# default.net
KiCad netlist of a schematic drawn in Altium Designer
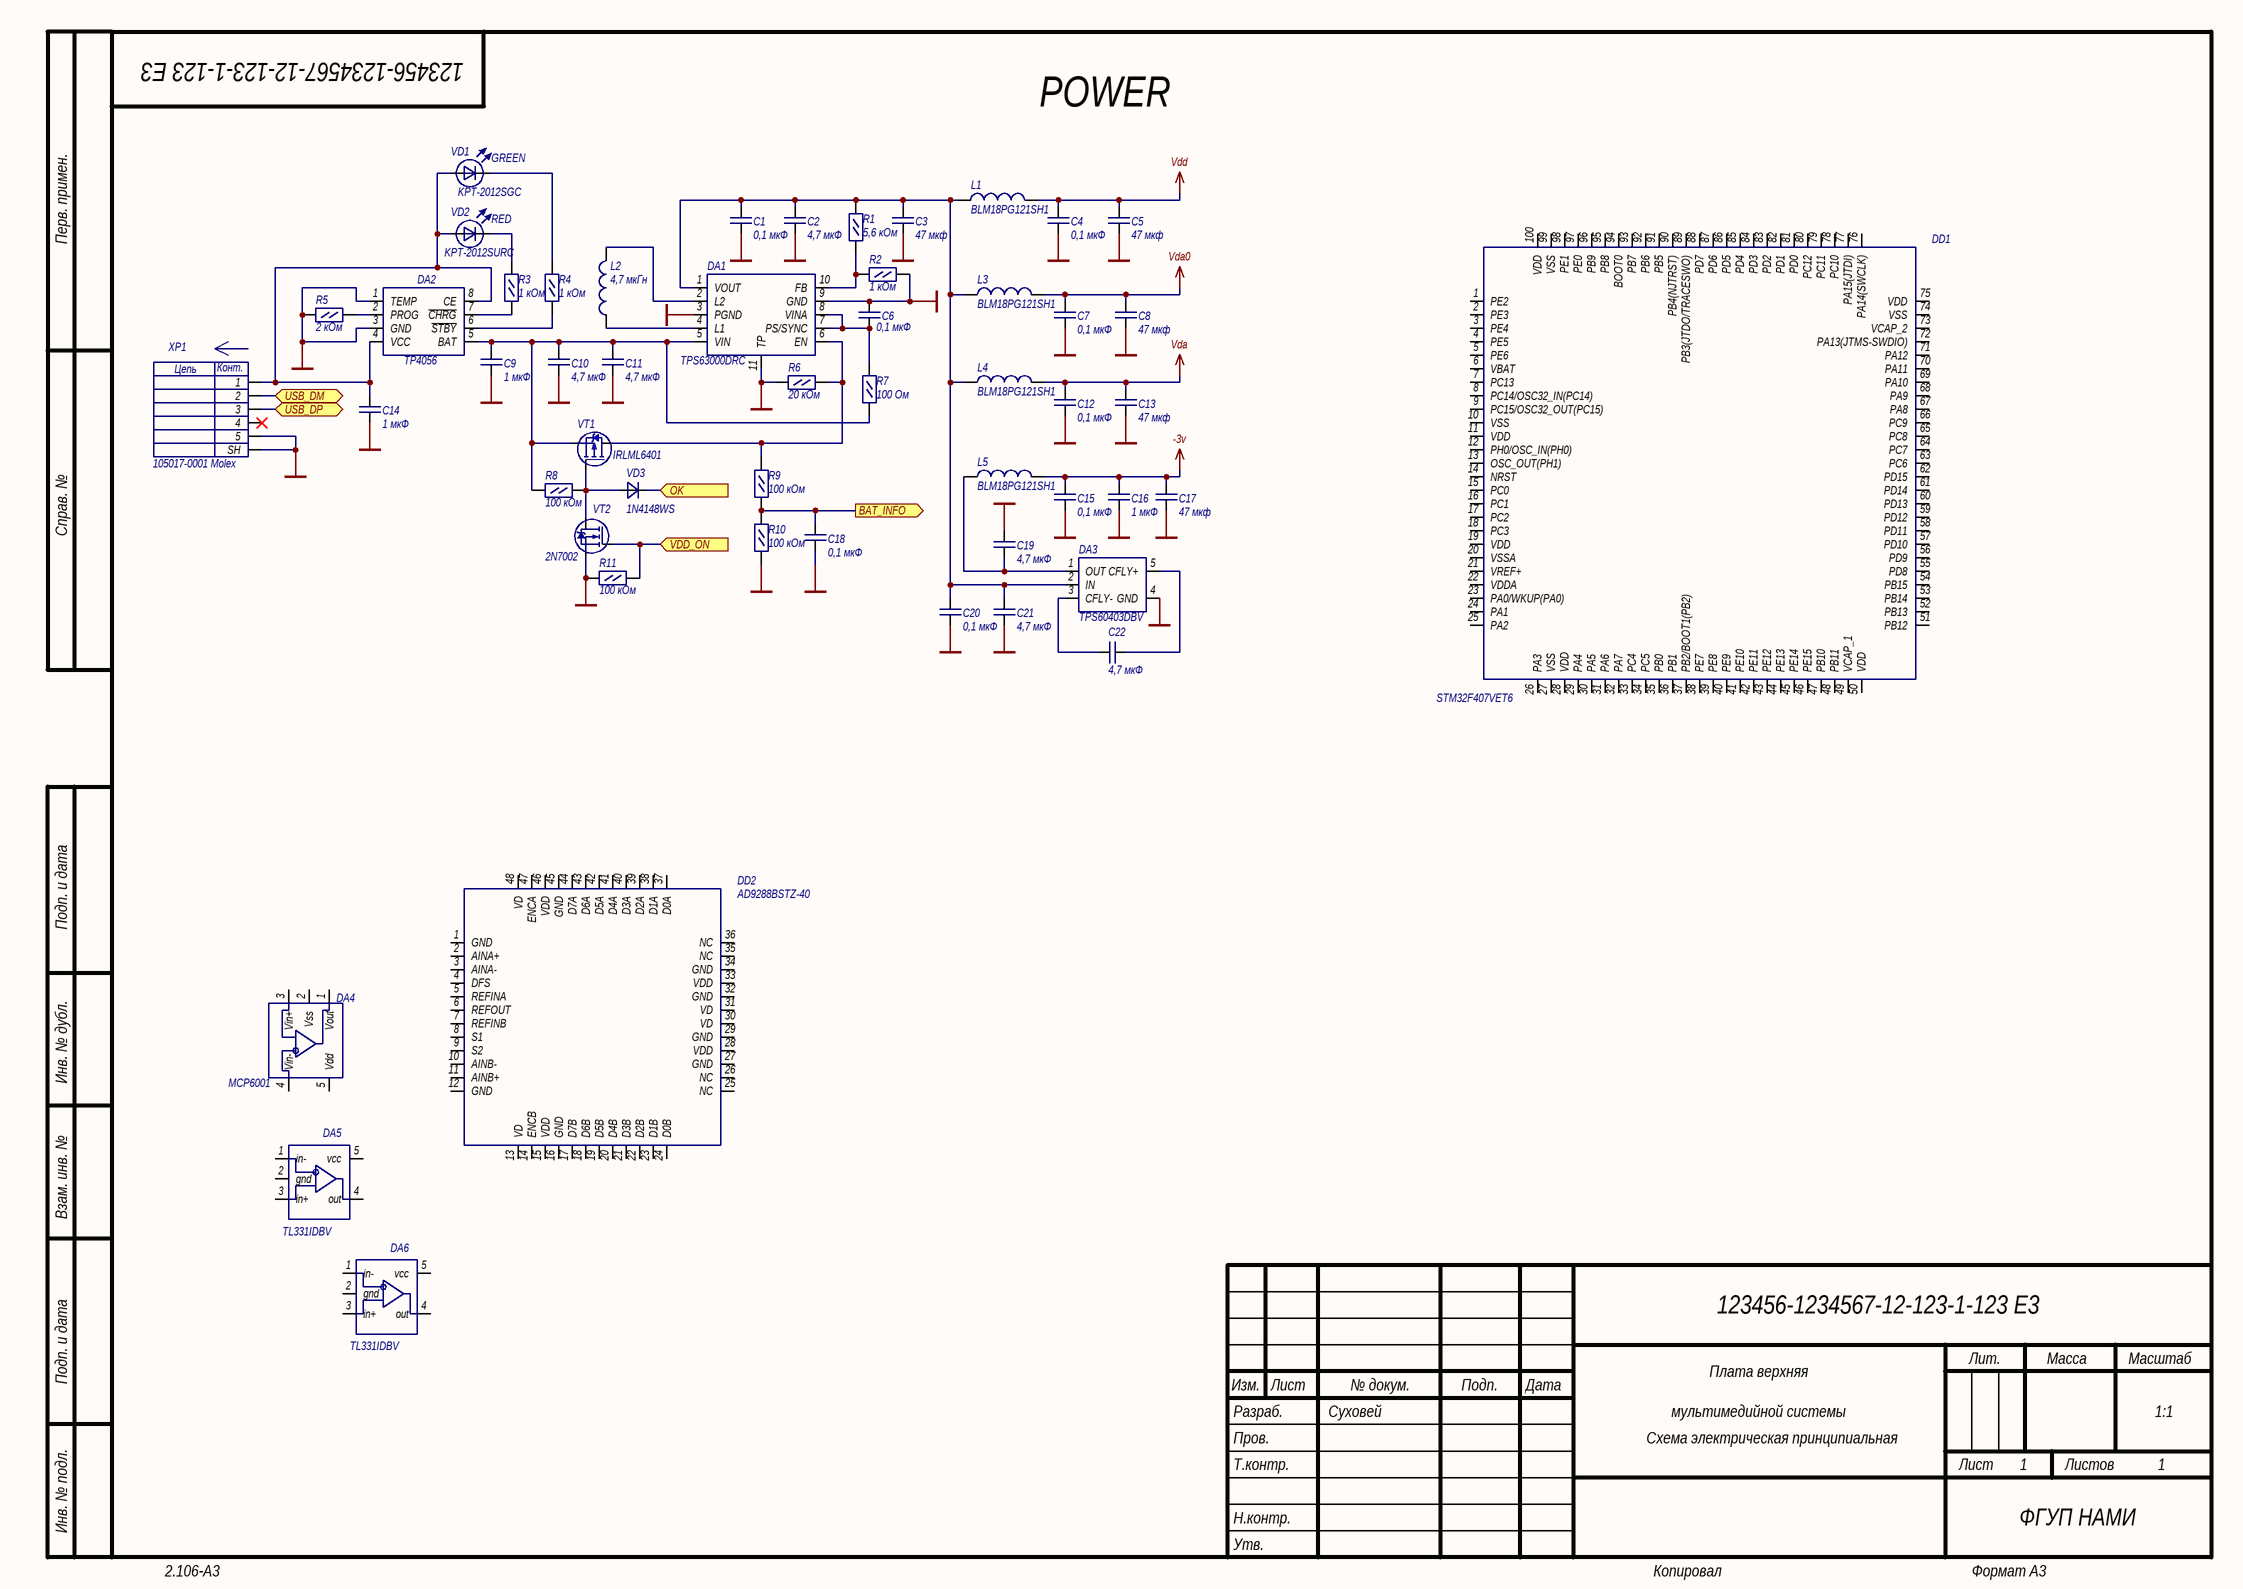
[diagram p0: default.SchDoc]

(export (version "E")
  (design (tool "Eeschema 10.0.6"))
  (components
    (comp (ref "C1")
      (value "0,1 мкФ")
      (footprint "CAP0603")
      (description "Конденсатор SMD 0603")
      (fields (field (name "TOLERANCE") "±10%") (field (name "MANUFACTURER") "Yageo"))
      (libsource (lib "sun_library2") (part "CAP"))
    )
    (comp (ref "C2")
      (value "4,7 мкФ")
      (footprint "CAP0603")
      (description "Конденсатор SMD 0603")
      (fields (field (name "TOLERANCE") "±10%") (field (name "MANUFACTURER") "Yageo"))
      (libsource (lib "sun_library2") (part "CAP"))
    )
    (comp (ref "C3")
      (value "47 мкф")
      (footprint "CAP1206")
      (description "Конденсатор керамический")
      (fields (field (name "TOLERANCE") "±20%") (field (name "MANUFACTURER") "Murata"))
      (libsource (lib "sun_library2") (part "CAP"))
    )
    (comp (ref "C4")
      (value "0,1 мкФ")
      (footprint "CAP0603")
      (description "Конденсатор SMD 0603")
      (fields (field (name "TOLERANCE") "±10%") (field (name "MANUFACTURER") "Yageo"))
      (libsource (lib "sun_library2") (part "CAP"))
    )
    (comp (ref "C5")
      (value "47 мкф")
      (footprint "CAP1206")
      (description "Конденсатор керамический")
      (fields (field (name "TOLERANCE") "±20%") (field (name "MANUFACTURER") "Murata"))
      (libsource (lib "sun_library2") (part "CAP"))
    )
    (comp (ref "C6")
      (value "0,1 мкФ")
      (footprint "CAP0603")
      (description "Конденсатор SMD 0603")
      (fields (field (name "TOLERANCE") "±10%") (field (name "MANUFACTURER") "Yageo"))
      (libsource (lib "sun_library2") (part "CAP"))
    )
    (comp (ref "C7")
      (value "0,1 мкФ")
      (footprint "CAP0603")
      (description "Конденсатор SMD 0603")
      (fields (field (name "TOLERANCE") "±10%") (field (name "MANUFACTURER") "Yageo"))
      (libsource (lib "sun_library2") (part "CAP"))
    )
    (comp (ref "C8")
      (value "47 мкф")
      (footprint "CAP1206")
      (description "Конденсатор керамический")
      (fields (field (name "TOLERANCE") "±20%") (field (name "MANUFACTURER") "Murata"))
      (libsource (lib "sun_library2") (part "CAP"))
    )
    (comp (ref "C9")
      (value "1 мкФ")
      (footprint "CAP0603")
      (description "Конденсатор SMD 0603")
      (fields (field (name "TOLERANCE") "±10%") (field (name "MANUFACTURER") "Yageo"))
      (libsource (lib "sun_library2") (part "CAP"))
    )
    (comp (ref "C10")
      (value "4,7 мкФ")
      (footprint "CAP0603")
      (description "Конденсатор SMD 0603")
      (fields (field (name "TOLERANCE") "±10%") (field (name "MANUFACTURER") "Yageo"))
      (libsource (lib "sun_library2") (part "CAP"))
    )
    (comp (ref "C11")
      (value "4,7 мкФ")
      (footprint "CAP0603")
      (description "Конденсатор SMD 0603")
      (fields (field (name "TOLERANCE") "±10%") (field (name "MANUFACTURER") "Yageo"))
      (libsource (lib "sun_library2") (part "CAP"))
    )
    (comp (ref "C12")
      (value "0,1 мкФ")
      (footprint "CAP0603")
      (description "Конденсатор SMD 0603")
      (fields (field (name "TOLERANCE") "±10%") (field (name "MANUFACTURER") "Yageo"))
      (libsource (lib "sun_library2") (part "CAP"))
    )
    (comp (ref "C13")
      (value "47 мкф")
      (footprint "CAP1206")
      (description "Конденсатор керамический")
      (fields (field (name "TOLERANCE") "±20%") (field (name "MANUFACTURER") "Murata"))
      (libsource (lib "sun_library2") (part "CAP"))
    )
    (comp (ref "C14")
      (value "1 мкФ")
      (footprint "CAP0603")
      (description "Конденсатор SMD 0603")
      (fields (field (name "TOLERANCE") "±10%") (field (name "MANUFACTURER") "Yageo"))
      (libsource (lib "sun_library2") (part "CAP"))
    )
    (comp (ref "C15")
      (value "0,1 мкФ")
      (footprint "CAP0603")
      (description "Конденсатор SMD 0603")
      (fields (field (name "TOLERANCE") "±10%") (field (name "MANUFACTURER") "Yageo"))
      (libsource (lib "sun_library2") (part "CAP"))
    )
    (comp (ref "C16")
      (value "1 мкФ")
      (footprint "CAP0603")
      (description "Конденсатор SMD 0603")
      (fields (field (name "TOLERANCE") "±10%") (field (name "MANUFACTURER") "Yageo"))
      (libsource (lib "sun_library2") (part "CAP"))
    )
    (comp (ref "C17")
      (value "47 мкф")
      (footprint "CAP1206")
      (description "Конденсатор керамический")
      (fields (field (name "TOLERANCE") "±20%") (field (name "MANUFACTURER") "Murata"))
      (libsource (lib "sun_library2") (part "CAP"))
    )
    (comp (ref "C18")
      (value "0,1 мкФ")
      (footprint "CAP0603")
      (description "Конденсатор SMD 0603")
      (fields (field (name "TOLERANCE") "±10%") (field (name "MANUFACTURER") "Yageo"))
      (libsource (lib "sun_library2") (part "CAP"))
    )
    (comp (ref "C19")
      (value "4,7 мкФ")
      (footprint "CAP0603")
      (description "Конденсатор SMD 0603")
      (fields (field (name "TOLERANCE") "±10%") (field (name "MANUFACTURER") "Yageo"))
      (libsource (lib "sun_library2") (part "CAP"))
    )
    (comp (ref "C20")
      (value "0,1 мкФ")
      (footprint "CAP0603")
      (description "Конденсатор SMD 0603")
      (fields (field (name "TOLERANCE") "±10%") (field (name "MANUFACTURER") "Yageo"))
      (libsource (lib "sun_library2") (part "CAP"))
    )
    (comp (ref "C21")
      (value "4,7 мкФ")
      (footprint "CAP0603")
      (description "Конденсатор SMD 0603")
      (fields (field (name "TOLERANCE") "±10%") (field (name "MANUFACTURER") "Yageo"))
      (libsource (lib "sun_library2") (part "CAP"))
    )
    (comp (ref "C22")
      (value "4,7 мкФ")
      (footprint "CAP0603")
      (description "Конденсатор SMD 0603")
      (fields (field (name "TOLERANCE") "±10%") (field (name "MANUFACTURER") "Yageo"))
      (libsource (lib "sun_library2") (part "CAP"))
    )
    (comp (ref "DA1")
      (value "TPS63000DRC")
      (footprint "SON10")
      (description "Микросхема")
      (fields (field (name "MANUFACTURER") "Texas Instruments"))
      (libsource (lib "sun_library2") (part "TPS63000"))
    )
    (comp (ref "DA2")
      (value "TP4056")
      (footprint "SO8_PAD")
      (description "Микросхема")
      (fields
        (field (name "MANUFACTURER") "NanJing Top Power")
        (field (name "PART NUMBER") "TP4056-42-SOP8-PP")
      )
      (libsource (lib "sun_library2") (part "TP4056"))
    )
    (comp (ref "DA3")
      (value "TPS60403DBV")
      (footprint "SOT23-5")
      (description "Микросхема")
      (fields (field (name "MANUFACTURER") "Texas Instruments"))
      (libsource (lib "sun_library2") (part "TPS60403"))
    )
    (comp (ref "DA4")
      (value "MCP6001")
      (footprint "SOT23-5")
      (description "Микросхема")
      (fields (field (name "MANUFACTURER") "Microchip") (field (name "PART NUMBER") "MCP6001RT-E/OT"))
      (libsource (lib "sun_library2") (part "MCP6001"))
    )
    (comp (ref "DA5")
      (value "TL331IDBV")
      (footprint "SOT23-5")
      (description "Микросхема")
      (fields (field (name "MANUFACTURER") "Texas Instruments"))
      (libsource (lib "sun_library2") (part "TL331IDBV"))
    )
    (comp (ref "DA6")
      (value "TL331IDBV")
      (footprint "SOT23-5")
      (description "Микросхема")
      (fields (field (name "MANUFACTURER") "Texas Instruments"))
      (libsource (lib "sun_library2") (part "TL331IDBV"))
    )
    (comp (ref "DD1")
      (value "STM32F407VET6")
      (footprint "QFP100P50_1600X1600X160L60X22N")
      (description "Микросхема")
      (fields (field (name "MANUFACTURER") "STMicroelectronics"))
      (libsource (lib "sun_library2") (part "STM32F407V"))
    )
    (comp (ref "DD2")
      (value "AD9288BSTZ-40")
      (footprint "TQFP48_L")
      (description "Микросхема")
      (fields (field (name "MANUFACTURER") "Analog Devices"))
      (libsource (lib "sun_library2") (part "AD9288BSTZ"))
    )
    (comp (ref "L1")
      (value "BLM18PG121SH1")
      (footprint "L0603")
      (description "Фильтр ЭМП")
      (fields (field (name "MANUFACTURER") "Murata"))
      (libsource (lib "sun_library2") (part "INDUCTOR"))
    )
    (comp (ref "L2")
      (value "4,7 мкГн")
      (footprint "SRP4020")
      (description "Дроссель")
      (fields (field (name "MANUFACTURER") "Bourns") (field (name "PART NUMBER") "SRP4020TA-4R7M"))
      (libsource (lib "sun_library2") (part "INDUCTOR"))
    )
    (comp (ref "L3")
      (value "BLM18PG121SH1")
      (footprint "L0603")
      (description "Фильтр ЭМП")
      (fields (field (name "MANUFACTURER") "Murata"))
      (libsource (lib "sun_library2") (part "INDUCTOR"))
    )
    (comp (ref "L4")
      (value "BLM18PG121SH1")
      (footprint "L0603")
      (description "Фильтр ЭМП")
      (fields (field (name "MANUFACTURER") "Murata"))
      (libsource (lib "sun_library2") (part "INDUCTOR"))
    )
    (comp (ref "L5")
      (value "BLM18PG121SH1")
      (footprint "L0603")
      (description "Фильтр ЭМП")
      (fields (field (name "MANUFACTURER") "Murata"))
      (libsource (lib "sun_library2") (part "INDUCTOR"))
    )
    (comp (ref "R1")
      (value "5,6 кОм")
      (footprint "RES0603")
      (description "Резистор SMD 0603")
      (fields (field (name "TOLERANCE") "±5%") (field (name "MANUFACTURER") "YAGEO"))
      (libsource (lib "") (part "RES_0.125_2"))
    )
    (comp (ref "R2")
      (value "1 кОм")
      (footprint "RES0603")
      (description "Резистор SMD 0603")
      (fields (field (name "TOLERANCE") "±5%") (field (name "MANUFACTURER") "YAGEO"))
      (libsource (lib "sun_library2") (part "RES_0.125"))
    )
    (comp (ref "R3")
      (value "1 кОм")
      (footprint "RES0603")
      (description "Резистор SMD 0603")
      (fields (field (name "TOLERANCE") "±5%") (field (name "MANUFACTURER") "YAGEO"))
      (libsource (lib "") (part "RES_0.125_2"))
    )
    (comp (ref "R4")
      (value "1 кОм")
      (footprint "RES0603")
      (description "Резистор SMD 0603")
      (fields (field (name "TOLERANCE") "±5%") (field (name "MANUFACTURER") "YAGEO"))
      (libsource (lib "") (part "RES_0.125_2"))
    )
    (comp (ref "R5")
      (value "2 кОм")
      (footprint "RES0603")
      (description "Резистор SMD 0603")
      (fields (field (name "TOLERANCE") "±5%") (field (name "MANUFACTURER") "YAGEO"))
      (libsource (lib "") (part "RES_0.125_1"))
    )
    (comp (ref "R6")
      (value "20 кОм")
      (footprint "RES0603")
      (description "Резистор SMD 0603")
      (fields (field (name "TOLERANCE") "±5%") (field (name "MANUFACTURER") "YAGEO"))
      (libsource (lib "") (part "RES_0.125_1"))
    )
    (comp (ref "R7")
      (value "100 Ом")
      (footprint "RES0603")
      (description "Резистор SMD 0603")
      (fields (field (name "TOLERANCE") "±5%") (field (name "MANUFACTURER") "YAGEO"))
      (libsource (lib "") (part "RES_0.125_2"))
    )
    (comp (ref "R8")
      (value "100 кОм")
      (footprint "RES0603")
      (description "Резистор SMD 0603")
      (fields (field (name "TOLERANCE") "±5%") (field (name "MANUFACTURER") "YAGEO"))
      (libsource (lib "") (part "RES_0.125_1"))
    )
    (comp (ref "R9")
      (value "100 кОм")
      (footprint "RES0603")
      (description "Резистор SMD 0603")
      (fields (field (name "TOLERANCE") "±5%") (field (name "MANUFACTURER") "YAGEO"))
      (libsource (lib "") (part "RES_0.125_2"))
    )
    (comp (ref "R10")
      (value "100 кОм")
      (footprint "RES0603")
      (description "Резистор SMD 0603")
      (fields (field (name "TOLERANCE") "±5%") (field (name "MANUFACTURER") "YAGEO"))
      (libsource (lib "") (part "RES_0.125_2"))
    )
    (comp (ref "R11")
      (value "100 кОм")
      (footprint "RES0603")
      (description "Резистор SMD 0603")
      (fields (field (name "TOLERANCE") "±5%") (field (name "MANUFACTURER") "YAGEO"))
      (libsource (lib "") (part "RES_0.125_1"))
    )
    (comp (ref "VD1")
      (value "GREEN")
      (footprint "LED-0805 GREEN")
      (description "Светодиод")
      (fields
        (field (name "ALTIUM_VALUE") "KPT-2012SGC")
        (field (name "MANUFACTURER") "Kingbright")
        (field (name "PART NUMBER") "KPT-2012SGC")
      )
      (libsource (lib "sun_library2") (part "LED"))
    )
    (comp (ref "VD2")
      (value "RED")
      (footprint "LED-0805 RED")
      (description "Светодиод")
      (fields
        (field (name "ALTIUM_VALUE") "KPT-2012SURC")
        (field (name "MANUFACTURER") "Kingbright")
        (field (name "PART NUMBER") "KPT-2012SURC")
      )
      (libsource (lib "sun_library2") (part "LED"))
    )
    (comp (ref "VD3")
      (value "1N4148WS")
      (footprint "SOD323")
      (description "Диод")
      (fields (field (name "MANUFACTURER") "Diodes"))
      (libsource (lib "sun_library2") (part "DIODE"))
    )
    (comp (ref "VT1")
      (value "IRLML6401")
      (footprint "SOT23")
      (description "Транзистор")
      (fields (field (name "MANUFACTURER") "Infineon") (field (name "VOLTAGE") "12V 3,4A 50mOhm"))
      (libsource (lib "sun_library2") (part "P-MOSFET"))
    )
    (comp (ref "VT2")
      (value "2N7002")
      (footprint "SOT23")
      (description "Транзистор")
      (fields (field (name "MANUFACTURER") "NXP"))
      (libsource (lib "sun_library2") (part "N-MOSFET_GSD"))
    )
    (comp (ref "XP1")
      (value "105017-0001 Molex")
      (footprint "USB_MICRO")
      (description "Разъем")
      (fields (field (name "MANUFACTURER") "Molex") (field (name "PART NUMBER") "105017-0001"))
      (libsource (lib "sun_library2") (part "CON_USB_MICRO"))
    )
  )
  (nets
    (net (code "1") (name "-3v") (class "Default")
      (node (ref "C15") (pin "1") (pintype "passive"))
      (node (ref "C16") (pin "1") (pintype "passive"))
      (node (ref "C17") (pin "1") (pintype "passive"))
      (node (ref "L5") (pin "2") (pinfunction "2_2") (pintype "passive"))
    )
    (net (code "2") (name "/BAT_INFO") (class "Default")
      (node (ref "C18") (pin "1") (pintype "passive"))
      (node (ref "R10") (pin "2") (pinfunction "2_2") (pintype "passive"))
      (node (ref "R9") (pin "1") (pinfunction "1_1") (pintype "passive"))
    )
    (net (code "3") (name "/OK") (class "Default")
      (node (ref "VD3") (pin "C") (pinfunction "C_C") (pintype "passive"))
    )
    (net (code "4") (name "/USB_DM") (class "Default")
      (node (ref "XP1") (pin "2") (pinfunction "2_2") (pintype "passive"))
    )
    (net (code "5") (name "/USB_DP") (class "Default")
      (node (ref "XP1") (pin "3") (pinfunction "3_3") (pintype "passive"))
    )
    (net (code "6") (name "/VDD_ON") (class "Default")
      (node (ref "R11") (pin "2") (pinfunction "2_2") (pintype "passive"))
      (node (ref "VT2") (pin "1") (pinfunction "G_1") (pintype "passive"))
    )
    (net (code "7") (name "GND") (class "Default")
      (node (ref "C1") (pin "2") (pintype "passive"))
      (node (ref "C10") (pin "2") (pintype "passive"))
      (node (ref "C11") (pin "2") (pintype "passive"))
      (node (ref "C12") (pin "2") (pintype "passive"))
      (node (ref "C13") (pin "2") (pintype "passive"))
      (node (ref "C14") (pin "2") (pintype "passive"))
      (node (ref "C15") (pin "2") (pintype "passive"))
      (node (ref "C16") (pin "2") (pintype "passive"))
      (node (ref "C17") (pin "2") (pintype "passive"))
      (node (ref "C18") (pin "2") (pintype "passive"))
      (node (ref "C19") (pin "2") (pintype "passive"))
      (node (ref "C2") (pin "2") (pintype "passive"))
      (node (ref "C20") (pin "2") (pintype "passive"))
      (node (ref "C21") (pin "2") (pintype "passive"))
      (node (ref "C3") (pin "2") (pintype "passive"))
      (node (ref "C4") (pin "2") (pintype "passive"))
      (node (ref "C5") (pin "2") (pintype "passive"))
      (node (ref "C6") (pin "1") (pintype "passive"))
      (node (ref "C7") (pin "2") (pintype "passive"))
      (node (ref "C8") (pin "2") (pintype "passive"))
      (node (ref "C9") (pin "2") (pintype "passive"))
      (node (ref "DA1") (pin "11") (pinfunction "TP_11") (pintype "passive"))
      (node (ref "DA1") (pin "3") (pinfunction "PGND_3") (pintype "passive"))
      (node (ref "DA1") (pin "9") (pinfunction "GND_9") (pintype "passive"))
      (node (ref "DA2") (pin "1") (pinfunction "TEMP_1") (pintype "passive"))
      (node (ref "DA2") (pin "3") (pinfunction "GND_3") (pintype "passive"))
      (node (ref "DA3") (pin "4") (pinfunction "GND_4") (pintype "passive"))
      (node (ref "R10") (pin "1") (pinfunction "1_1") (pintype "passive"))
      (node (ref "R11") (pin "1") (pinfunction "1_1") (pintype "passive"))
      (node (ref "R2") (pin "1") (pinfunction "1_1") (pintype "passive"))
      (node (ref "R5") (pin "1") (pinfunction "1_1") (pintype "passive"))
      (node (ref "R6") (pin "1") (pinfunction "1_1") (pintype "passive"))
      (node (ref "VT2") (pin "2") (pinfunction "S_2") (pintype "passive"))
      (node (ref "XP1") (pin "5") (pinfunction "5_5") (pintype "passive"))
      (node (ref "XP1") (pin "SH") (pinfunction "SH_SH") (pintype "passive"))
    )
    (net (code "8") (name "Net-(DA1-EN)") (class "Default")
      (node (ref "DA1") (pin "6") (pinfunction "EN_6") (pintype "passive"))
      (node (ref "R6") (pin "2") (pinfunction "2_2") (pintype "passive"))
      (node (ref "R9") (pin "2") (pinfunction "2_2") (pintype "passive"))
      (node (ref "VT1") (pin "2") (pinfunction "D_2") (pintype "passive"))
    )
    (net (code "9") (name "Net-(DA1-FB)") (class "Default")
      (node (ref "DA1") (pin "10") (pinfunction "FB_10") (pintype "passive"))
      (node (ref "R1") (pin "1") (pinfunction "1_1") (pintype "passive"))
      (node (ref "R2") (pin "2") (pinfunction "2_2") (pintype "passive"))
    )
    (net (code "10") (name "Net-(DA1-L1)") (class "Default")
      (node (ref "DA1") (pin "4") (pinfunction "L1_4") (pintype "passive"))
      (node (ref "L2") (pin "1") (pinfunction "1_1") (pintype "passive"))
    )
    (net (code "11") (name "Net-(DA1-L2)") (class "Default")
      (node (ref "DA1") (pin "2") (pinfunction "L2_2") (pintype "passive"))
      (node (ref "L2") (pin "2") (pinfunction "2_2") (pintype "passive"))
    )
    (net (code "12") (name "Net-(DA1-PS{slash}SYNC)") (class "Default")
      (node (ref "C6") (pin "2") (pintype "passive"))
      (node (ref "DA1") (pin "7") (pinfunction "PS/SYNC_7") (pintype "passive"))
      (node (ref "DA1") (pin "8") (pinfunction "VINA_8") (pintype "passive"))
      (node (ref "R7") (pin "2") (pinfunction "2_2") (pintype "passive"))
    )
    (net (code "13") (name "Net-(DA1-VIN)") (class "Default")
      (node (ref "C10") (pin "1") (pintype "passive"))
      (node (ref "C11") (pin "1") (pintype "passive"))
      (node (ref "C9") (pin "1") (pintype "passive"))
      (node (ref "DA1") (pin "5") (pinfunction "VIN_5") (pintype "passive"))
      (node (ref "DA2") (pin "5") (pinfunction "BAT_5") (pintype "power_in"))
      (node (ref "R7") (pin "1") (pinfunction "1_1") (pintype "passive"))
      (node (ref "R8") (pin "1") (pinfunction "1_1") (pintype "passive"))
      (node (ref "VT1") (pin "3") (pinfunction "S_3") (pintype "passive"))
    )
    (net (code "14") (name "Net-(DA1-VOUT)") (class "Default")
      (node (ref "C1") (pin "1") (pintype "passive"))
      (node (ref "C2") (pin "1") (pintype "passive"))
      (node (ref "C20") (pin "1") (pintype "passive"))
      (node (ref "C21") (pin "1") (pintype "passive"))
      (node (ref "C3") (pin "1") (pintype "passive"))
      (node (ref "DA1") (pin "1") (pinfunction "VOUT_1") (pintype "passive"))
      (node (ref "DA3") (pin "2") (pinfunction "IN_2") (pintype "power_in"))
      (node (ref "L1") (pin "1") (pinfunction "1_1") (pintype "passive"))
      (node (ref "L3") (pin "1") (pinfunction "1_1") (pintype "passive"))
      (node (ref "L4") (pin "1") (pinfunction "1_1") (pintype "passive"))
      (node (ref "R1") (pin "2") (pinfunction "2_2") (pintype "passive"))
    )
    (net (code "15") (name "Net-(DA2-CE)") (class "Default")
      (node (ref "C14") (pin "1") (pintype "passive"))
      (node (ref "DA2") (pin "4") (pinfunction "VCC_4") (pintype "passive"))
      (node (ref "DA2") (pin "8") (pinfunction "CE_8") (pintype "power_in"))
      (node (ref "VD1") (pin "A") (pinfunction "A_A") (pintype "passive"))
      (node (ref "VD2") (pin "A") (pinfunction "A_A") (pintype "passive"))
      (node (ref "XP1") (pin "1") (pinfunction "1_1") (pintype "passive"))
    )
    (net (code "16") (name "Net-(DA2-PROG)") (class "Default")
      (node (ref "DA2") (pin "2") (pinfunction "PROG_2") (pintype "power_in"))
      (node (ref "R5") (pin "2") (pinfunction "2_2") (pintype "passive"))
    )
    (net (code "17") (name "Net-(DA2-~{CHRG})") (class "Default")
      (node (ref "DA2") (pin "7") (pinfunction "~{CHRG}_7") (pintype "passive"))
      (node (ref "R3") (pin "1") (pinfunction "1_1") (pintype "passive"))
    )
    (net (code "18") (name "Net-(DA2-~{STBY})") (class "Default")
      (node (ref "DA2") (pin "6") (pinfunction "~{STBY}_6") (pintype "passive"))
      (node (ref "R4") (pin "1") (pinfunction "1_1") (pintype "passive"))
    )
    (net (code "19") (name "Net-(DA3-CFLY+)") (class "Default")
      (node (ref "C22") (pin "2") (pintype "passive"))
      (node (ref "DA3") (pin "5") (pinfunction "CFLY+_5") (pintype "passive"))
    )
    (net (code "20") (name "Net-(DA3-CFLY-)") (class "Default")
      (node (ref "C22") (pin "1") (pintype "passive"))
      (node (ref "DA3") (pin "3") (pinfunction "CFLY-_3") (pintype "passive"))
    )
    (net (code "21") (name "Net-(DA3-OUT)") (class "Default")
      (node (ref "C19") (pin "1") (pintype "passive"))
      (node (ref "DA3") (pin "1") (pinfunction "OUT_1") (pintype "power_in"))
      (node (ref "L5") (pin "1") (pinfunction "1_1") (pintype "passive"))
    )
    (net (code "22") (name "Net-(R3-Pad2)") (class "Default")
      (node (ref "R3") (pin "2") (pinfunction "2_2") (pintype "passive"))
      (node (ref "VD2") (pin "C") (pinfunction "C_C") (pintype "passive"))
    )
    (net (code "23") (name "Net-(R4-Pad2)") (class "Default")
      (node (ref "R4") (pin "2") (pinfunction "2_2") (pintype "passive"))
      (node (ref "VD1") (pin "C") (pinfunction "C_C") (pintype "passive"))
    )
    (net (code "24") (name "Net-(VT1-G)") (class "Default")
      (node (ref "R8") (pin "2") (pinfunction "2_2") (pintype "passive"))
      (node (ref "VD3") (pin "A") (pinfunction "A_A") (pintype "passive"))
      (node (ref "VT1") (pin "1") (pinfunction "G_1") (pintype "passive"))
      (node (ref "VT2") (pin "3") (pinfunction "D_3") (pintype "passive"))
    )
    (net (code "25") (name "Vda") (class "Default")
      (node (ref "C12") (pin "1") (pintype "passive"))
      (node (ref "C13") (pin "1") (pintype "passive"))
      (node (ref "L4") (pin "2") (pinfunction "2_2") (pintype "passive"))
    )
    (net (code "26") (name "Vda0") (class "Default")
      (node (ref "C7") (pin "1") (pintype "passive"))
      (node (ref "C8") (pin "1") (pintype "passive"))
      (node (ref "L3") (pin "2") (pinfunction "2_2") (pintype "passive"))
    )
    (net (code "27") (name "Vdd") (class "Default")
      (node (ref "C4") (pin "1") (pintype "passive"))
      (node (ref "C5") (pin "1") (pintype "passive"))
      (node (ref "L1") (pin "2") (pinfunction "2_2") (pintype "passive"))
    )
    (net (code "28") (name "unconnected-(DA4-Vdd-Pad5)") (class "Default")
      (node (ref "DA4") (pin "5") (pinfunction "Vdd_5") (pintype "passive"))
    )
    (net (code "29") (name "unconnected-(DA4-Vin+-Pad3)") (class "Default")
      (node (ref "DA4") (pin "3") (pinfunction "Vin+_3") (pintype "passive"))
    )
    (net (code "30") (name "unconnected-(DA4-Vin--Pad4)") (class "Default")
      (node (ref "DA4") (pin "4") (pinfunction "Vin-_4") (pintype "passive"))
    )
    (net (code "31") (name "unconnected-(DA4-Vout-Pad1)") (class "Default")
      (node (ref "DA4") (pin "1") (pinfunction "Vout_1") (pintype "power_in"))
    )
    (net (code "32") (name "unconnected-(DA4-Vss-Pad2)") (class "Default")
      (node (ref "DA4") (pin "2") (pinfunction "Vss_2") (pintype "passive"))
    )
    (net (code "33") (name "unconnected-(DA5-gnd-Pad2)") (class "Default")
      (node (ref "DA5") (pin "2") (pinfunction "gnd_2") (pintype "passive"))
    )
    (net (code "34") (name "unconnected-(DA5-in+-Pad3)") (class "Default")
      (node (ref "DA5") (pin "3") (pinfunction "in+_3") (pintype "passive"))
    )
    (net (code "35") (name "unconnected-(DA5-in--Pad1)") (class "Default")
      (node (ref "DA5") (pin "1") (pinfunction "in-_1") (pintype "power_in"))
    )
    (net (code "36") (name "unconnected-(DA5-out-Pad4)") (class "Default")
      (node (ref "DA5") (pin "4") (pinfunction "out_4") (pintype "passive"))
    )
    (net (code "37") (name "unconnected-(DA5-vcc-Pad5)") (class "Default")
      (node (ref "DA5") (pin "5") (pinfunction "vcc_5") (pintype "passive"))
    )
    (net (code "38") (name "unconnected-(DA6-gnd-Pad2)") (class "Default")
      (node (ref "DA6") (pin "2") (pinfunction "gnd_2") (pintype "passive"))
    )
    (net (code "39") (name "unconnected-(DA6-in+-Pad3)") (class "Default")
      (node (ref "DA6") (pin "3") (pinfunction "in+_3") (pintype "passive"))
    )
    (net (code "40") (name "unconnected-(DA6-in--Pad1)") (class "Default")
      (node (ref "DA6") (pin "1") (pinfunction "in-_1") (pintype "power_in"))
    )
    (net (code "41") (name "unconnected-(DA6-out-Pad4)") (class "Default")
      (node (ref "DA6") (pin "4") (pinfunction "out_4") (pintype "passive"))
    )
    (net (code "42") (name "unconnected-(DA6-vcc-Pad5)") (class "Default")
      (node (ref "DA6") (pin "5") (pinfunction "vcc_5") (pintype "passive"))
    )
    (net (code "43") (name "unconnected-(DD1-BOOT0-Pad94)") (class "Default")
      (node (ref "DD1") (pin "94") (pinfunction "BOOT0_94") (pintype "passive"))
    )
    (net (code "44") (name "unconnected-(DD1-NRST-Pad14)") (class "Default")
      (node (ref "DD1") (pin "14") (pinfunction "NRST_14") (pintype "passive"))
    )
    (net (code "45") (name "unconnected-(DD1-OSC_OUT(PH1)-Pad13)") (class "Default")
      (node (ref "DD1") (pin "13") (pinfunction "OSC_OUT(PH1)_13") (pintype "passive"))
    )
    (net (code "46") (name "unconnected-(DD1-PA0{slash}WKUP(PA0)-Pad23)") (class "Default")
      (node (ref "DD1") (pin "23") (pinfunction "PA0/WKUP(PA0)_23") (pintype "passive"))
    )
    (net (code "47") (name "unconnected-(DD1-PA1-Pad24)") (class "Default")
      (node (ref "DD1") (pin "24") (pinfunction "PA1_24") (pintype "passive"))
    )
    (net (code "48") (name "unconnected-(DD1-PA2-Pad25)") (class "Default")
      (node (ref "DD1") (pin "25") (pinfunction "PA2_25") (pintype "passive"))
    )
    (net (code "49") (name "unconnected-(DD1-PA3-Pad26)") (class "Default")
      (node (ref "DD1") (pin "26") (pinfunction "PA3_26") (pintype "passive"))
    )
    (net (code "50") (name "unconnected-(DD1-PA4-Pad29)") (class "Default")
      (node (ref "DD1") (pin "29") (pinfunction "PA4_29") (pintype "passive"))
    )
    (net (code "51") (name "unconnected-(DD1-PA5-Pad30)") (class "Default")
      (node (ref "DD1") (pin "30") (pinfunction "PA5_30") (pintype "passive"))
    )
    (net (code "52") (name "unconnected-(DD1-PA6-Pad31)") (class "Default")
      (node (ref "DD1") (pin "31") (pinfunction "PA6_31") (pintype "passive"))
    )
    (net (code "53") (name "unconnected-(DD1-PA7-Pad32)") (class "Default")
      (node (ref "DD1") (pin "32") (pinfunction "PA7_32") (pintype "passive"))
    )
    (net (code "54") (name "unconnected-(DD1-PA8-Pad67)") (class "Default")
      (node (ref "DD1") (pin "67") (pinfunction "PA8_67") (pintype "passive"))
    )
    (net (code "55") (name "unconnected-(DD1-PA9-Pad68)") (class "Default")
      (node (ref "DD1") (pin "68") (pinfunction "PA9_68") (pintype "passive"))
    )
    (net (code "56") (name "unconnected-(DD1-PA10-Pad69)") (class "Default")
      (node (ref "DD1") (pin "69") (pinfunction "PA10_69") (pintype "passive"))
    )
    (net (code "57") (name "unconnected-(DD1-PA11-Pad70)") (class "Default")
      (node (ref "DD1") (pin "70") (pinfunction "PA11_70") (pintype "passive"))
    )
    (net (code "58") (name "unconnected-(DD1-PA12-Pad71)") (class "Default")
      (node (ref "DD1") (pin "71") (pinfunction "PA12_71") (pintype "passive"))
    )
    (net (code "59") (name "unconnected-(DD1-PA13(JTMS-SWDIO)-Pad72)") (class "Default")
      (node (ref "DD1") (pin "72") (pinfunction "PA13(JTMS-SWDIO)_72") (pintype "passive"))
    )
    (net (code "60") (name "unconnected-(DD1-PA14(SWCLK)-Pad76)") (class "Default")
      (node (ref "DD1") (pin "76") (pinfunction "PA14(SWCLK)_76") (pintype "passive"))
    )
    (net (code "61") (name "unconnected-(DD1-PA15(JTDI)-Pad77)") (class "Default")
      (node (ref "DD1") (pin "77") (pinfunction "PA15(JTDI)_77") (pintype "passive"))
    )
    (net (code "62") (name "unconnected-(DD1-PB0-Pad35)") (class "Default")
      (node (ref "DD1") (pin "35") (pinfunction "PB0_35") (pintype "passive"))
    )
    (net (code "63") (name "unconnected-(DD1-PB1-Pad36)") (class "Default")
      (node (ref "DD1") (pin "36") (pinfunction "PB1_36") (pintype "passive"))
    )
    (net (code "64") (name "unconnected-(DD1-PB2{slash}BOOT1(PB2)-Pad37)") (class "Default")
      (node (ref "DD1") (pin "37") (pinfunction "PB2/BOOT1(PB2)_37") (pintype "passive"))
    )
    (net (code "65") (name "unconnected-(DD1-PB3(JTDO{slash}TRACESWO)-Pad89)") (class "Default")
      (node (ref "DD1") (pin "89") (pinfunction "PB3(JTDO/TRACESWO)_89") (pintype "passive"))
    )
    (net (code "66") (name "unconnected-(DD1-PB4(NJTRST)-Pad90)") (class "Default")
      (node (ref "DD1") (pin "90") (pinfunction "PB4(NJTRST)_90") (pintype "passive"))
    )
    (net (code "67") (name "unconnected-(DD1-PB5-Pad91)") (class "Default")
      (node (ref "DD1") (pin "91") (pinfunction "PB5_91") (pintype "passive"))
    )
    (net (code "68") (name "unconnected-(DD1-PB6-Pad92)") (class "Default")
      (node (ref "DD1") (pin "92") (pinfunction "PB6_92") (pintype "passive"))
    )
    (net (code "69") (name "unconnected-(DD1-PB7-Pad93)") (class "Default")
      (node (ref "DD1") (pin "93") (pinfunction "PB7_93") (pintype "passive"))
    )
    (net (code "70") (name "unconnected-(DD1-PB8-Pad95)") (class "Default")
      (node (ref "DD1") (pin "95") (pinfunction "PB8_95") (pintype "passive"))
    )
    (net (code "71") (name "unconnected-(DD1-PB9-Pad96)") (class "Default")
      (node (ref "DD1") (pin "96") (pinfunction "PB9_96") (pintype "passive"))
    )
    (net (code "72") (name "unconnected-(DD1-PB10-Pad47)") (class "Default")
      (node (ref "DD1") (pin "47") (pinfunction "PB10_47") (pintype "passive"))
    )
    (net (code "73") (name "unconnected-(DD1-PB11-Pad48)") (class "Default")
      (node (ref "DD1") (pin "48") (pinfunction "PB11_48") (pintype "passive"))
    )
    (net (code "74") (name "unconnected-(DD1-PB12-Pad51)") (class "Default")
      (node (ref "DD1") (pin "51") (pinfunction "PB12_51") (pintype "passive"))
    )
    (net (code "75") (name "unconnected-(DD1-PB13-Pad52)") (class "Default")
      (node (ref "DD1") (pin "52") (pinfunction "PB13_52") (pintype "passive"))
    )
    (net (code "76") (name "unconnected-(DD1-PB14-Pad53)") (class "Default")
      (node (ref "DD1") (pin "53") (pinfunction "PB14_53") (pintype "passive"))
    )
    (net (code "77") (name "unconnected-(DD1-PB15-Pad54)") (class "Default")
      (node (ref "DD1") (pin "54") (pinfunction "PB15_54") (pintype "passive"))
    )
    (net (code "78") (name "unconnected-(DD1-PC0-Pad15)") (class "Default")
      (node (ref "DD1") (pin "15") (pinfunction "PC0_15") (pintype "passive"))
    )
    (net (code "79") (name "unconnected-(DD1-PC1-Pad16)") (class "Default")
      (node (ref "DD1") (pin "16") (pinfunction "PC1_16") (pintype "passive"))
    )
    (net (code "80") (name "unconnected-(DD1-PC2-Pad17)") (class "Default")
      (node (ref "DD1") (pin "17") (pinfunction "PC2_17") (pintype "passive"))
    )
    (net (code "81") (name "unconnected-(DD1-PC3-Pad18)") (class "Default")
      (node (ref "DD1") (pin "18") (pinfunction "PC3_18") (pintype "passive"))
    )
    (net (code "82") (name "unconnected-(DD1-PC4-Pad33)") (class "Default")
      (node (ref "DD1") (pin "33") (pinfunction "PC4_33") (pintype "passive"))
    )
    (net (code "83") (name "unconnected-(DD1-PC5-Pad34)") (class "Default")
      (node (ref "DD1") (pin "34") (pinfunction "PC5_34") (pintype "passive"))
    )
    (net (code "84") (name "unconnected-(DD1-PC6-Pad63)") (class "Default")
      (node (ref "DD1") (pin "63") (pinfunction "PC6_63") (pintype "passive"))
    )
    (net (code "85") (name "unconnected-(DD1-PC7-Pad64)") (class "Default")
      (node (ref "DD1") (pin "64") (pinfunction "PC7_64") (pintype "passive"))
    )
    (net (code "86") (name "unconnected-(DD1-PC8-Pad65)") (class "Default")
      (node (ref "DD1") (pin "65") (pinfunction "PC8_65") (pintype "passive"))
    )
    (net (code "87") (name "unconnected-(DD1-PC9-Pad66)") (class "Default")
      (node (ref "DD1") (pin "66") (pinfunction "PC9_66") (pintype "passive"))
    )
    (net (code "88") (name "unconnected-(DD1-PC10-Pad78)") (class "Default")
      (node (ref "DD1") (pin "78") (pinfunction "PC10_78") (pintype "passive"))
    )
    (net (code "89") (name "unconnected-(DD1-PC11-Pad79)") (class "Default")
      (node (ref "DD1") (pin "79") (pinfunction "PC11_79") (pintype "passive"))
    )
    (net (code "90") (name "unconnected-(DD1-PC12-Pad80)") (class "Default")
      (node (ref "DD1") (pin "80") (pinfunction "PC12_80") (pintype "passive"))
    )
    (net (code "91") (name "unconnected-(DD1-PC13-Pad7)") (class "Default")
      (node (ref "DD1") (pin "7") (pinfunction "PC13_7") (pintype "passive"))
    )
    (net (code "92") (name "unconnected-(DD1-PC14{slash}OSC32_IN(PC14)-Pad8)") (class "Default")
      (node (ref "DD1") (pin "8") (pinfunction "PC14/OSC32_IN(PC14)_8") (pintype "passive"))
    )
    (net (code "93") (name "unconnected-(DD1-PC15{slash}OSC32_OUT(PC15)-Pad9)") (class "Default")
      (node (ref "DD1") (pin "9") (pinfunction "PC15/OSC32_OUT(PC15)_9") (pintype "passive"))
    )
    (net (code "94") (name "unconnected-(DD1-PD0-Pad81)") (class "Default")
      (node (ref "DD1") (pin "81") (pinfunction "PD0_81") (pintype "passive"))
    )
    (net (code "95") (name "unconnected-(DD1-PD1-Pad82)") (class "Default")
      (node (ref "DD1") (pin "82") (pinfunction "PD1_82") (pintype "passive"))
    )
    (net (code "96") (name "unconnected-(DD1-PD2-Pad83)") (class "Default")
      (node (ref "DD1") (pin "83") (pinfunction "PD2_83") (pintype "passive"))
    )
    (net (code "97") (name "unconnected-(DD1-PD3-Pad84)") (class "Default")
      (node (ref "DD1") (pin "84") (pinfunction "PD3_84") (pintype "passive"))
    )
    (net (code "98") (name "unconnected-(DD1-PD4-Pad85)") (class "Default")
      (node (ref "DD1") (pin "85") (pinfunction "PD4_85") (pintype "passive"))
    )
    (net (code "99") (name "unconnected-(DD1-PD5-Pad86)") (class "Default")
      (node (ref "DD1") (pin "86") (pinfunction "PD5_86") (pintype "passive"))
    )
    (net (code "100") (name "unconnected-(DD1-PD6-Pad87)") (class "Default")
      (node (ref "DD1") (pin "87") (pinfunction "PD6_87") (pintype "passive"))
    )
    (net (code "101") (name "unconnected-(DD1-PD7-Pad88)") (class "Default")
      (node (ref "DD1") (pin "88") (pinfunction "PD7_88") (pintype "passive"))
    )
    (net (code "102") (name "unconnected-(DD1-PD8-Pad55)") (class "Default")
      (node (ref "DD1") (pin "55") (pinfunction "PD8_55") (pintype "passive"))
    )
    (net (code "103") (name "unconnected-(DD1-PD9-Pad56)") (class "Default")
      (node (ref "DD1") (pin "56") (pinfunction "PD9_56") (pintype "passive"))
    )
    (net (code "104") (name "unconnected-(DD1-PD10-Pad57)") (class "Default")
      (node (ref "DD1") (pin "57") (pinfunction "PD10_57") (pintype "passive"))
    )
    (net (code "105") (name "unconnected-(DD1-PD11-Pad58)") (class "Default")
      (node (ref "DD1") (pin "58") (pinfunction "PD11_58") (pintype "passive"))
    )
    (net (code "106") (name "unconnected-(DD1-PD12-Pad59)") (class "Default")
      (node (ref "DD1") (pin "59") (pinfunction "PD12_59") (pintype "passive"))
    )
    (net (code "107") (name "unconnected-(DD1-PD13-Pad60)") (class "Default")
      (node (ref "DD1") (pin "60") (pinfunction "PD13_60") (pintype "passive"))
    )
    (net (code "108") (name "unconnected-(DD1-PD14-Pad61)") (class "Default")
      (node (ref "DD1") (pin "61") (pinfunction "PD14_61") (pintype "passive"))
    )
    (net (code "109") (name "unconnected-(DD1-PD15-Pad62)") (class "Default")
      (node (ref "DD1") (pin "62") (pinfunction "PD15_62") (pintype "passive"))
    )
    (net (code "110") (name "unconnected-(DD1-PE0-Pad97)") (class "Default")
      (node (ref "DD1") (pin "97") (pinfunction "PE0_97") (pintype "passive"))
    )
    (net (code "111") (name "unconnected-(DD1-PE1-Pad98)") (class "Default")
      (node (ref "DD1") (pin "98") (pinfunction "PE1_98") (pintype "passive"))
    )
    (net (code "112") (name "unconnected-(DD1-PE2-Pad1)") (class "Default")
      (node (ref "DD1") (pin "1") (pinfunction "PE2_1") (pintype "passive"))
    )
    (net (code "113") (name "unconnected-(DD1-PE3-Pad2)") (class "Default")
      (node (ref "DD1") (pin "2") (pinfunction "PE3_2") (pintype "passive"))
    )
    (net (code "114") (name "unconnected-(DD1-PE4-Pad3)") (class "Default")
      (node (ref "DD1") (pin "3") (pinfunction "PE4_3") (pintype "passive"))
    )
    (net (code "115") (name "unconnected-(DD1-PE5-Pad4)") (class "Default")
      (node (ref "DD1") (pin "4") (pinfunction "PE5_4") (pintype "passive"))
    )
    (net (code "116") (name "unconnected-(DD1-PE6-Pad5)") (class "Default")
      (node (ref "DD1") (pin "5") (pinfunction "PE6_5") (pintype "passive"))
    )
    (net (code "117") (name "unconnected-(DD1-PE7-Pad38)") (class "Default")
      (node (ref "DD1") (pin "38") (pinfunction "PE7_38") (pintype "passive"))
    )
    (net (code "118") (name "unconnected-(DD1-PE8-Pad39)") (class "Default")
      (node (ref "DD1") (pin "39") (pinfunction "PE8_39") (pintype "passive"))
    )
    (net (code "119") (name "unconnected-(DD1-PE9-Pad40)") (class "Default")
      (node (ref "DD1") (pin "40") (pinfunction "PE9_40") (pintype "passive"))
    )
    (net (code "120") (name "unconnected-(DD1-PE10-Pad41)") (class "Default")
      (node (ref "DD1") (pin "41") (pinfunction "PE10_41") (pintype "passive"))
    )
    (net (code "121") (name "unconnected-(DD1-PE11-Pad42)") (class "Default")
      (node (ref "DD1") (pin "42") (pinfunction "PE11_42") (pintype "passive"))
    )
    (net (code "122") (name "unconnected-(DD1-PE12-Pad43)") (class "Default")
      (node (ref "DD1") (pin "43") (pinfunction "PE12_43") (pintype "passive"))
    )
    (net (code "123") (name "unconnected-(DD1-PE13-Pad44)") (class "Default")
      (node (ref "DD1") (pin "44") (pinfunction "PE13_44") (pintype "passive"))
    )
    (net (code "124") (name "unconnected-(DD1-PE14-Pad45)") (class "Default")
      (node (ref "DD1") (pin "45") (pinfunction "PE14_45") (pintype "passive"))
    )
    (net (code "125") (name "unconnected-(DD1-PE15-Pad46)") (class "Default")
      (node (ref "DD1") (pin "46") (pinfunction "PE15_46") (pintype "passive"))
    )
    (net (code "126") (name "unconnected-(DD1-PH0{slash}OSC_IN(PH0)-Pad12)") (class "Default")
      (node (ref "DD1") (pin "12") (pinfunction "PH0/OSC_IN(PH0)_12") (pintype "passive"))
    )
    (net (code "127") (name "unconnected-(DD1-VBAT-Pad6)") (class "Default")
      (node (ref "DD1") (pin "6") (pinfunction "VBAT_6") (pintype "passive"))
    )
    (net (code "128") (name "unconnected-(DD1-VCAP_1-Pad49)") (class "Default")
      (node (ref "DD1") (pin "49") (pinfunction "VCAP_1_49") (pintype "passive"))
    )
    (net (code "129") (name "unconnected-(DD1-VCAP_2-Pad73)") (class "Default")
      (node (ref "DD1") (pin "73") (pinfunction "VCAP_2_73") (pintype "passive"))
    )
    (net (code "130") (name "unconnected-(DD1-VDD-Pad11)") (class "Default")
      (node (ref "DD1") (pin "11") (pinfunction "VDD_11") (pintype "passive"))
    )
    (net (code "131") (name "unconnected-(DD1-VDD-Pad19)") (class "Default")
      (node (ref "DD1") (pin "19") (pinfunction "VDD_19") (pintype "passive"))
    )
    (net (code "132") (name "unconnected-(DD1-VDD-Pad28)") (class "Default")
      (node (ref "DD1") (pin "28") (pinfunction "VDD_28") (pintype "passive"))
    )
    (net (code "133") (name "unconnected-(DD1-VDD-Pad50)") (class "Default")
      (node (ref "DD1") (pin "50") (pinfunction "VDD_50") (pintype "passive"))
    )
    (net (code "134") (name "unconnected-(DD1-VDD-Pad75)") (class "Default")
      (node (ref "DD1") (pin "75") (pinfunction "VDD_75") (pintype "passive"))
    )
    (net (code "135") (name "unconnected-(DD1-VDD-Pad100)") (class "Default")
      (node (ref "DD1") (pin "100") (pinfunction "VDD_100") (pintype "passive"))
    )
    (net (code "136") (name "unconnected-(DD1-VDDA-Pad22)") (class "Default")
      (node (ref "DD1") (pin "22") (pinfunction "VDDA_22") (pintype "passive"))
    )
    (net (code "137") (name "unconnected-(DD1-VREF+-Pad21)") (class "Default")
      (node (ref "DD1") (pin "21") (pinfunction "VREF+_21") (pintype "passive"))
    )
    (net (code "138") (name "unconnected-(DD1-VSS-Pad10)") (class "Default")
      (node (ref "DD1") (pin "10") (pinfunction "VSS_10") (pintype "passive"))
    )
    (net (code "139") (name "unconnected-(DD1-VSS-Pad27)") (class "Default")
      (node (ref "DD1") (pin "27") (pinfunction "VSS_27") (pintype "passive"))
    )
    (net (code "140") (name "unconnected-(DD1-VSS-Pad74)") (class "Default")
      (node (ref "DD1") (pin "74") (pinfunction "VSS_74") (pintype "passive"))
    )
    (net (code "141") (name "unconnected-(DD1-VSS-Pad99)") (class "Default")
      (node (ref "DD1") (pin "99") (pinfunction "VSS_99") (pintype "passive"))
    )
    (net (code "142") (name "unconnected-(DD1-VSSA-Pad20)") (class "Default")
      (node (ref "DD1") (pin "20") (pinfunction "VSSA_20") (pintype "passive"))
    )
    (net (code "143") (name "unconnected-(DD2-AINA+-Pad2)") (class "Default")
      (node (ref "DD2") (pin "2") (pinfunction "AINA+_2") (pintype "passive"))
    )
    (net (code "144") (name "unconnected-(DD2-AINA--Pad3)") (class "Default")
      (node (ref "DD2") (pin "3") (pinfunction "AINA-_3") (pintype "passive"))
    )
    (net (code "145") (name "unconnected-(DD2-AINB+-Pad11)") (class "Default")
      (node (ref "DD2") (pin "11") (pinfunction "AINB+_11") (pintype "passive"))
    )
    (net (code "146") (name "unconnected-(DD2-AINB--Pad10)") (class "Default")
      (node (ref "DD2") (pin "10") (pinfunction "AINB-_10") (pintype "passive"))
    )
    (net (code "147") (name "unconnected-(DD2-D0A-Pad37)") (class "Default")
      (node (ref "DD2") (pin "37") (pinfunction "D0A_37") (pintype "passive"))
    )
    (net (code "148") (name "unconnected-(DD2-D0B-Pad24)") (class "Default")
      (node (ref "DD2") (pin "24") (pinfunction "D0B_24") (pintype "passive"))
    )
    (net (code "149") (name "unconnected-(DD2-D1A-Pad38)") (class "Default")
      (node (ref "DD2") (pin "38") (pinfunction "D1A_38") (pintype "passive"))
    )
    (net (code "150") (name "unconnected-(DD2-D1B-Pad23)") (class "Default")
      (node (ref "DD2") (pin "23") (pinfunction "D1B_23") (pintype "passive"))
    )
    (net (code "151") (name "unconnected-(DD2-D2A-Pad39)") (class "Default")
      (node (ref "DD2") (pin "39") (pinfunction "D2A_39") (pintype "passive"))
    )
    (net (code "152") (name "unconnected-(DD2-D2B-Pad22)") (class "Default")
      (node (ref "DD2") (pin "22") (pinfunction "D2B_22") (pintype "passive"))
    )
    (net (code "153") (name "unconnected-(DD2-D3A-Pad40)") (class "Default")
      (node (ref "DD2") (pin "40") (pinfunction "D3A_40") (pintype "passive"))
    )
    (net (code "154") (name "unconnected-(DD2-D3B-Pad21)") (class "Default")
      (node (ref "DD2") (pin "21") (pinfunction "D3B_21") (pintype "passive"))
    )
    (net (code "155") (name "unconnected-(DD2-D4A-Pad41)") (class "Default")
      (node (ref "DD2") (pin "41") (pinfunction "D4A_41") (pintype "passive"))
    )
    (net (code "156") (name "unconnected-(DD2-D4B-Pad20)") (class "Default")
      (node (ref "DD2") (pin "20") (pinfunction "D4B_20") (pintype "passive"))
    )
    (net (code "157") (name "unconnected-(DD2-D5A-Pad42)") (class "Default")
      (node (ref "DD2") (pin "42") (pinfunction "D5A_42") (pintype "passive"))
    )
    (net (code "158") (name "unconnected-(DD2-D5B-Pad19)") (class "Default")
      (node (ref "DD2") (pin "19") (pinfunction "D5B_19") (pintype "passive"))
    )
    (net (code "159") (name "unconnected-(DD2-D6A-Pad43)") (class "Default")
      (node (ref "DD2") (pin "43") (pinfunction "D6A_43") (pintype "passive"))
    )
    (net (code "160") (name "unconnected-(DD2-D6B-Pad18)") (class "Default")
      (node (ref "DD2") (pin "18") (pinfunction "D6B_18") (pintype "passive"))
    )
    (net (code "161") (name "unconnected-(DD2-D7A-Pad44)") (class "Default")
      (node (ref "DD2") (pin "44") (pinfunction "D7A_44") (pintype "passive"))
    )
    (net (code "162") (name "unconnected-(DD2-D7B-Pad17)") (class "Default")
      (node (ref "DD2") (pin "17") (pinfunction "D7B_17") (pintype "passive"))
    )
    (net (code "163") (name "unconnected-(DD2-DFS-Pad4)") (class "Default")
      (node (ref "DD2") (pin "4") (pinfunction "DFS_4") (pintype "passive"))
    )
    (net (code "164") (name "unconnected-(DD2-ENCA-Pad47)") (class "Default")
      (node (ref "DD2") (pin "47") (pinfunction "ENCA_47") (pintype "passive"))
    )
    (net (code "165") (name "unconnected-(DD2-ENCB-Pad14)") (class "Default")
      (node (ref "DD2") (pin "14") (pinfunction "ENCB_14") (pintype "passive"))
    )
    (net (code "166") (name "unconnected-(DD2-GND-Pad1)") (class "Default")
      (node (ref "DD2") (pin "1") (pinfunction "GND_1") (pintype "passive"))
    )
    (net (code "167") (name "unconnected-(DD2-GND-Pad12)") (class "Default")
      (node (ref "DD2") (pin "12") (pinfunction "GND_12") (pintype "passive"))
    )
    (net (code "168") (name "unconnected-(DD2-GND-Pad16)") (class "Default")
      (node (ref "DD2") (pin "16") (pinfunction "GND_16") (pintype "passive"))
    )
    (net (code "169") (name "unconnected-(DD2-GND-Pad27)") (class "Default")
      (node (ref "DD2") (pin "27") (pinfunction "GND_27") (pintype "passive"))
    )
    (net (code "170") (name "unconnected-(DD2-GND-Pad29)") (class "Default")
      (node (ref "DD2") (pin "29") (pinfunction "GND_29") (pintype "passive"))
    )
    (net (code "171") (name "unconnected-(DD2-GND-Pad32)") (class "Default")
      (node (ref "DD2") (pin "32") (pinfunction "GND_32") (pintype "passive"))
    )
    (net (code "172") (name "unconnected-(DD2-GND-Pad34)") (class "Default")
      (node (ref "DD2") (pin "34") (pinfunction "GND_34") (pintype "passive"))
    )
    (net (code "173") (name "unconnected-(DD2-GND-Pad45)") (class "Default")
      (node (ref "DD2") (pin "45") (pinfunction "GND_45") (pintype "passive"))
    )
    (net (code "174") (name "unconnected-(DD2-NC-Pad25)") (class "Default")
      (node (ref "DD2") (pin "25") (pinfunction "NC_25") (pintype "passive"))
    )
    (net (code "175") (name "unconnected-(DD2-NC-Pad26)") (class "Default")
      (node (ref "DD2") (pin "26") (pinfunction "NC_26") (pintype "passive"))
    )
    (net (code "176") (name "unconnected-(DD2-NC-Pad35)") (class "Default")
      (node (ref "DD2") (pin "35") (pinfunction "NC_35") (pintype "passive"))
    )
    (net (code "177") (name "unconnected-(DD2-NC-Pad36)") (class "Default")
      (node (ref "DD2") (pin "36") (pinfunction "NC_36") (pintype "passive"))
    )
    (net (code "178") (name "unconnected-(DD2-REFINA-Pad5)") (class "Default")
      (node (ref "DD2") (pin "5") (pinfunction "REFINA_5") (pintype "passive"))
    )
    (net (code "179") (name "unconnected-(DD2-REFINB-Pad7)") (class "Default")
      (node (ref "DD2") (pin "7") (pinfunction "REFINB_7") (pintype "passive"))
    )
    (net (code "180") (name "unconnected-(DD2-REFOUT-Pad6)") (class "Default")
      (node (ref "DD2") (pin "6") (pinfunction "REFOUT_6") (pintype "passive"))
    )
    (net (code "181") (name "unconnected-(DD2-S1-Pad8)") (class "Default")
      (node (ref "DD2") (pin "8") (pinfunction "S1_8") (pintype "passive"))
    )
    (net (code "182") (name "unconnected-(DD2-S2-Pad9)") (class "Default")
      (node (ref "DD2") (pin "9") (pinfunction "S2_9") (pintype "passive"))
    )
    (net (code "183") (name "unconnected-(DD2-VD-Pad13)") (class "Default")
      (node (ref "DD2") (pin "13") (pinfunction "VD_13") (pintype "passive"))
    )
    (net (code "184") (name "unconnected-(DD2-VD-Pad30)") (class "Default")
      (node (ref "DD2") (pin "30") (pinfunction "VD_30") (pintype "passive"))
    )
    (net (code "185") (name "unconnected-(DD2-VD-Pad31)") (class "Default")
      (node (ref "DD2") (pin "31") (pinfunction "VD_31") (pintype "passive"))
    )
    (net (code "186") (name "unconnected-(DD2-VD-Pad48)") (class "Default")
      (node (ref "DD2") (pin "48") (pinfunction "VD_48") (pintype "passive"))
    )
    (net (code "187") (name "unconnected-(DD2-VDD-Pad15)") (class "Default")
      (node (ref "DD2") (pin "15") (pinfunction "VDD_15") (pintype "passive"))
    )
    (net (code "188") (name "unconnected-(DD2-VDD-Pad28)") (class "Default")
      (node (ref "DD2") (pin "28") (pinfunction "VDD_28") (pintype "passive"))
    )
    (net (code "189") (name "unconnected-(DD2-VDD-Pad33)") (class "Default")
      (node (ref "DD2") (pin "33") (pinfunction "VDD_33") (pintype "passive"))
    )
    (net (code "190") (name "unconnected-(DD2-VDD-Pad46)") (class "Default")
      (node (ref "DD2") (pin "46") (pinfunction "VDD_46") (pintype "passive"))
    )
    (net (code "191") (name "unconnected-(XP1-Pad4)") (class "Default")
      (node (ref "XP1") (pin "4") (pinfunction "4_4") (pintype "passive+no_connect"))
    )
  )
)
